# Sine_Filter.net
KiCad netlist of a schematic drawn in Altium Designer
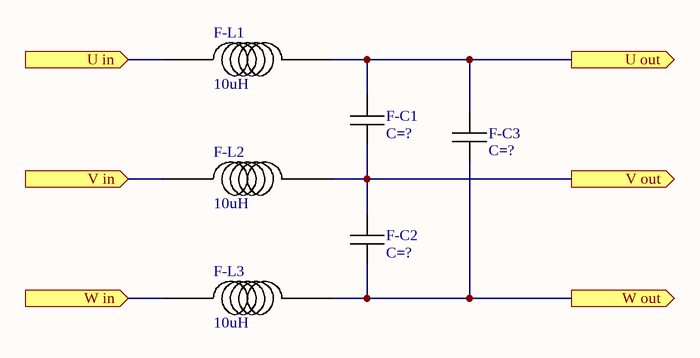
[diagram p0: Sine Filter.SchDoc]

(export (version "E")
  (design (tool "Eeschema 10.0.6"))
  (components
    (comp (ref "F-C1") (value "C=?") (libsource (lib "Standard") (part "Capacitor")))
    (comp (ref "F-C2") (value "C=?") (libsource (lib "Standard") (part "Capacitor")))
    (comp (ref "F-C3") (value "C=?") (libsource (lib "Standard") (part "Capacitor")))
    (comp (ref "F-L1")
      (value "10uH")
      (footprint "Header 1x2+1 1.0mm")
      (libsource (lib "Standard") (part "Coil"))
    )
    (comp (ref "F-L2")
      (value "10uH")
      (footprint "Header 1x2+1 1.0mm")
      (libsource (lib "Standard") (part "Coil"))
    )
    (comp (ref "F-L3")
      (value "10uH")
      (footprint "Header 1x2+1 1.0mm")
      (libsource (lib "Standard") (part "Coil"))
    )
  )
  (nets
    (net (code "1") (name "/U in") (class "Default")
      (node (ref "F-L1") (pin "1") (pinfunction "1_1") (pintype "passive"))
    )
    (net (code "2") (name "/U out") (class "Default")
      (node (ref "F-C1") (pin "1") (pinfunction "1_1") (pintype "passive"))
      (node (ref "F-C3") (pin "1") (pinfunction "1_1") (pintype "passive"))
      (node (ref "F-L1") (pin "2") (pinfunction "2_2") (pintype "passive"))
    )
    (net (code "3") (name "/V in") (class "Default")
      (node (ref "F-L2") (pin "1") (pinfunction "1_1") (pintype "passive"))
    )
    (net (code "4") (name "/V out") (class "Default")
      (node (ref "F-C1") (pin "2") (pinfunction "1_2") (pintype "passive"))
      (node (ref "F-C2") (pin "1") (pinfunction "1_1") (pintype "passive"))
      (node (ref "F-L2") (pin "2") (pinfunction "2_2") (pintype "passive"))
    )
    (net (code "5") (name "/W in") (class "Default")
      (node (ref "F-L3") (pin "1") (pinfunction "1_1") (pintype "passive"))
    )
    (net (code "6") (name "/W out") (class "Default")
      (node (ref "F-C2") (pin "2") (pinfunction "1_2") (pintype "passive"))
      (node (ref "F-C3") (pin "2") (pinfunction "1_2") (pintype "passive"))
      (node (ref "F-L3") (pin "2") (pinfunction "2_2") (pintype "passive"))
    )
  )
)
